# 3_ZynTra-Zynq-Config.net
KiCad netlist of a schematic drawn in Altium Designer
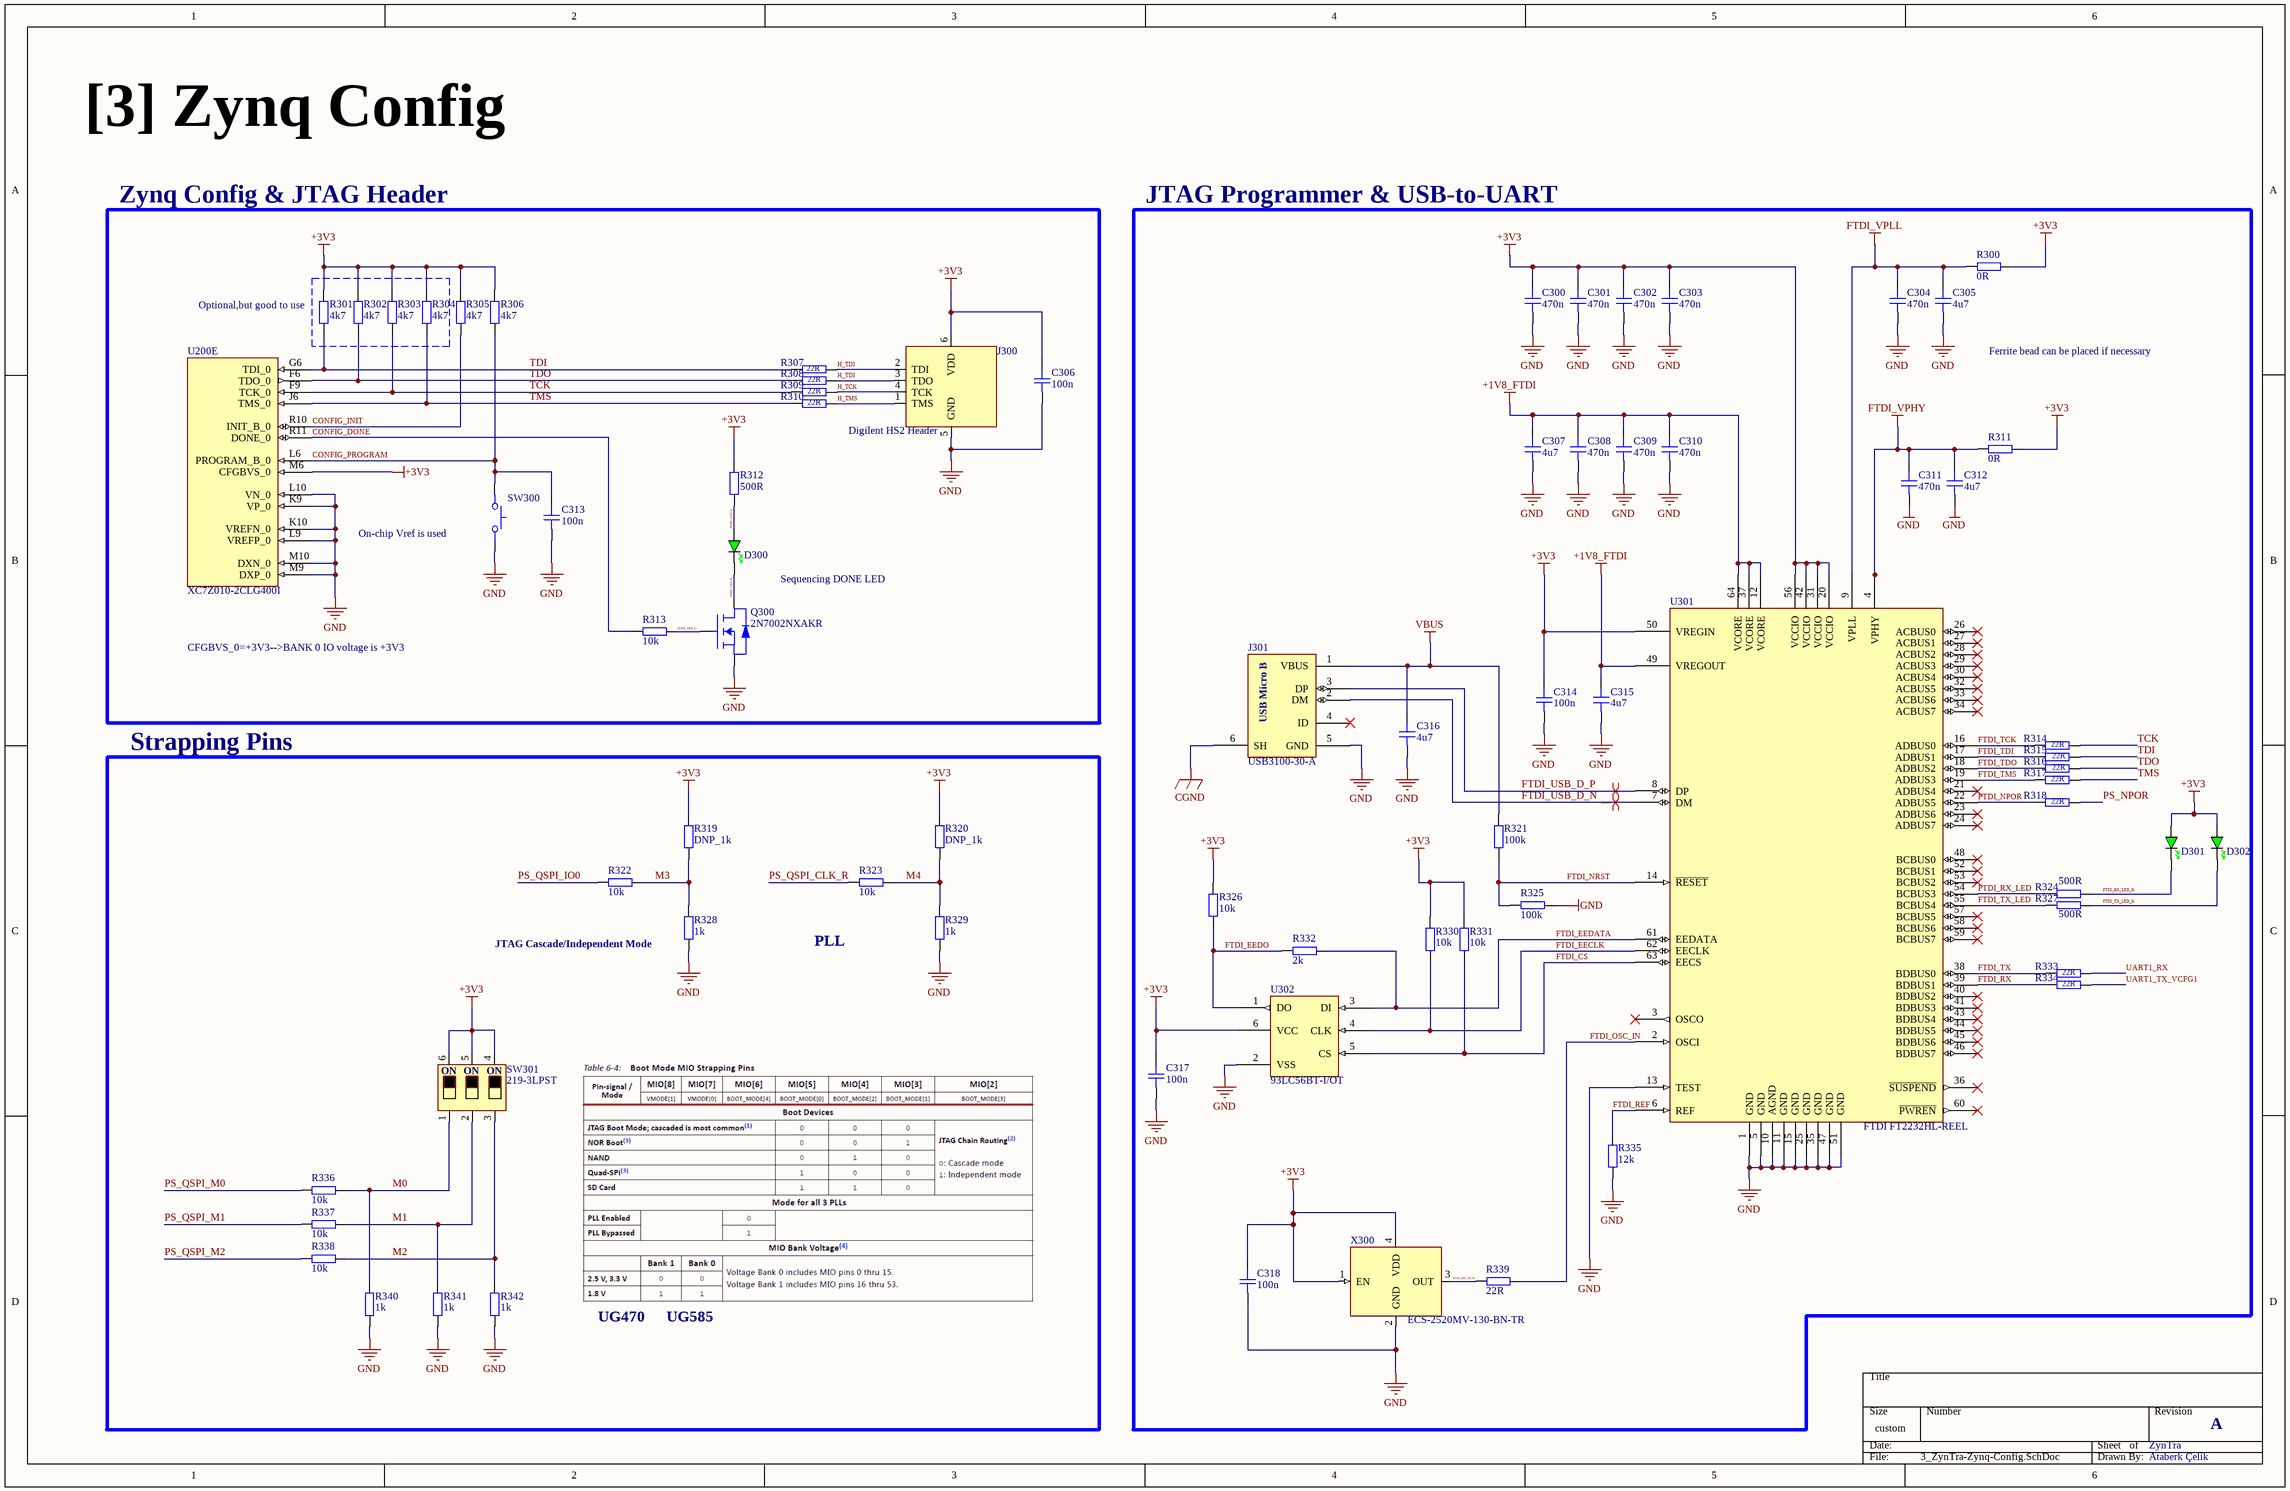
[diagram p0: 3_ZynTra-Zynq-Config.SchDoc]

(export (version "E")
  (design (tool "Eeschema 10.0.6"))
  (components
    (comp (ref "C300")
      (value "470n")
      (footprint "CAP_0201")
      (description "Capacitor SMD 0201")
      (libsource (lib "Schematic-Lib-PhilsLab") (part "CAP_0201"))
    )
    (comp (ref "C301")
      (value "470n")
      (footprint "CAP_0201")
      (description "Capacitor SMD 0201")
      (libsource (lib "Schematic-Lib-PhilsLab") (part "CAP_0201"))
    )
    (comp (ref "C302")
      (value "470n")
      (footprint "CAP_0201")
      (description "Capacitor SMD 0201")
      (libsource (lib "Schematic-Lib-PhilsLab") (part "CAP_0201"))
    )
    (comp (ref "C303")
      (value "470n")
      (footprint "CAP_0201")
      (description "Capacitor SMD 0201")
      (libsource (lib "Schematic-Lib-PhilsLab") (part "CAP_0201"))
    )
    (comp (ref "C304")
      (value "470n")
      (footprint "CAP_0201")
      (description "Capacitor SMD 0201")
      (libsource (lib "Schematic-Lib-PhilsLab") (part "CAP_0201"))
    )
    (comp (ref "C305")
      (value "4u7")
      (footprint "CAP_0402")
      (description "Capacitor SMD 0402")
      (libsource (lib "Schematic-Lib-PhilsLab") (part "CAP_0402"))
    )
    (comp (ref "C306")
      (value "100n")
      (footprint "CAP_0201")
      (description "Capacitor SMD 0201")
      (libsource (lib "Schematic-Lib-PhilsLab") (part "CAP_0201"))
    )
    (comp (ref "C307")
      (value "4u7")
      (footprint "CAP_0402")
      (description "Capacitor SMD 0402")
      (libsource (lib "Schematic-Lib-PhilsLab") (part "CAP_0402"))
    )
    (comp (ref "C308")
      (value "470n")
      (footprint "CAP_0201")
      (description "Capacitor SMD 0201")
      (libsource (lib "Schematic-Lib-PhilsLab") (part "CAP_0201"))
    )
    (comp (ref "C309")
      (value "470n")
      (footprint "CAP_0201")
      (description "Capacitor SMD 0201")
      (libsource (lib "Schematic-Lib-PhilsLab") (part "CAP_0201"))
    )
    (comp (ref "C310")
      (value "470n")
      (footprint "CAP_0201")
      (description "Capacitor SMD 0201")
      (libsource (lib "Schematic-Lib-PhilsLab") (part "CAP_0201"))
    )
    (comp (ref "C311")
      (value "470n")
      (footprint "CAP_0201")
      (description "Capacitor SMD 0201")
      (libsource (lib "Schematic-Lib-PhilsLab") (part "CAP_0201"))
    )
    (comp (ref "C312")
      (value "4u7")
      (footprint "CAP_0402")
      (description "Capacitor SMD 0402")
      (libsource (lib "Schematic-Lib-PhilsLab") (part "CAP_0402"))
    )
    (comp (ref "C313")
      (value "100n")
      (footprint "CAP_0201")
      (description "Capacitor SMD 0201")
      (libsource (lib "Schematic-Lib-PhilsLab") (part "CAP_0201"))
    )
    (comp (ref "C314")
      (value "100n")
      (footprint "CAP_0201")
      (description "Capacitor SMD 0201")
      (libsource (lib "Schematic-Lib-PhilsLab") (part "CAP_0201"))
    )
    (comp (ref "C315")
      (value "4u7")
      (footprint "CAP_0402")
      (description "Capacitor SMD 0402")
      (libsource (lib "Schematic-Lib-PhilsLab") (part "CAP_0402"))
    )
    (comp (ref "C316")
      (value "4u7")
      (footprint "CAP_0402")
      (description "Capacitor SMD 0402")
      (libsource (lib "Schematic-Lib-PhilsLab") (part "CAP_0402"))
    )
    (comp (ref "C317")
      (value "100n")
      (footprint "CAP_0201")
      (description "Capacitor SMD 0201")
      (libsource (lib "Schematic-Lib-PhilsLab") (part "CAP_0201"))
    )
    (comp (ref "C318")
      (value "100n")
      (footprint "CAP_0201")
      (description "Capacitor SMD 0201")
      (libsource (lib "Schematic-Lib-PhilsLab") (part "CAP_0201"))
    )
    (comp (ref "D300")
      (value "GREEN")
      (footprint "LED_0603_GREEN")
      (description "LED 0603 GREEN SMD")
      (libsource (lib "Schematic-Lib-PhilsLab") (part "LED_0603_GREEN"))
    )
    (comp (ref "D301")
      (value "GREEN")
      (footprint "LED_0603_GREEN")
      (description "LED 0603 GREEN SMD")
      (libsource (lib "Schematic-Lib-PhilsLab") (part "LED_0603_GREEN"))
    )
    (comp (ref "D302")
      (value "GREEN")
      (footprint "LED_0603_GREEN")
      (description "LED 0603 GREEN SMD")
      (libsource (lib "Schematic-Lib-PhilsLab") (part "LED_0603_GREEN"))
    )
    (comp (ref "J300")
      (value "Digilent HS2 Header")
      (footprint "DIGILENT_HS2")
      (description "Digilent HS2 6-Pin 2.54mm Pitch Header")
      (fields
        (field (name "MANUFACTURER") "Amphenol FCI")
        (field (name "MANUFACTURER PART NUMBER") "68000-406HLF")
      )
      (libsource (lib "Schematic-Lib-PhilsLab") (part "Digilent_HS2_Header"))
    )
    (comp (ref "J301")
      (value "USB3100-30-A")
      (footprint "USB3100-30-A")
      (description "Micro USB Receptacle, Type B, Surface Mount, Horizontal")
      (libsource (lib "AtaSchLib") (part "USB3100-30-A"))
    )
    (comp (ref "Q300")
      (value "2N7002NXAKR")
      (footprint "SSM3J338R,LF-SOT23-F")
      (description "MOSFET N-Channel Vds=60V Id=300mA with ESD Protection")
      (fields (field (name "MANUFACTURER") "Nexperia"))
      (libsource (lib "Schematic-Lib-PhilsLab") (part "2N7002NXAKR"))
    )
    (comp (ref "R300")
      (value "0R")
      (footprint "RES_0402")
      (description "Resistor SMD 0402")
      (libsource (lib "Schematic-Lib-PhilsLab") (part "RES_0402"))
    )
    (comp (ref "R301")
      (value "4k7")
      (footprint "RES_0201")
      (description "Resistor SMD 0201")
      (libsource (lib "Schematic-Lib-PhilsLab") (part "RES_0201"))
    )
    (comp (ref "R302")
      (value "4k7")
      (footprint "RES_0201")
      (description "Resistor SMD 0201")
      (libsource (lib "Schematic-Lib-PhilsLab") (part "RES_0201"))
    )
    (comp (ref "R303")
      (value "4k7")
      (footprint "RES_0201")
      (description "Resistor SMD 0201")
      (libsource (lib "Schematic-Lib-PhilsLab") (part "RES_0201"))
    )
    (comp (ref "R304")
      (value "4k7")
      (footprint "RES_0201")
      (description "Resistor SMD 0201")
      (libsource (lib "Schematic-Lib-PhilsLab") (part "RES_0201"))
    )
    (comp (ref "R305")
      (value "4k7")
      (footprint "RES_0201")
      (description "Resistor SMD 0201")
      (libsource (lib "Schematic-Lib-PhilsLab") (part "RES_0201"))
    )
    (comp (ref "R306")
      (value "4k7")
      (footprint "RES_0201")
      (description "Resistor SMD 0201")
      (libsource (lib "Schematic-Lib-PhilsLab") (part "RES_0201"))
    )
    (comp (ref "R307")
      (value "22R")
      (footprint "RES_0402")
      (description "Resistor SMD 0402")
      (libsource (lib "Schematic-Lib-PhilsLab") (part "RES_0402"))
    )
    (comp (ref "R308")
      (value "22R")
      (footprint "RES_0402")
      (description "Resistor SMD 0402")
      (libsource (lib "Schematic-Lib-PhilsLab") (part "RES_0402"))
    )
    (comp (ref "R309")
      (value "22R")
      (footprint "RES_0402")
      (description "Resistor SMD 0402")
      (libsource (lib "Schematic-Lib-PhilsLab") (part "RES_0402"))
    )
    (comp (ref "R310")
      (value "22R")
      (footprint "RES_0402")
      (description "Resistor SMD 0402")
      (libsource (lib "Schematic-Lib-PhilsLab") (part "RES_0402"))
    )
    (comp (ref "R311")
      (value "0R")
      (footprint "RES_0402")
      (description "Resistor SMD 0402")
      (libsource (lib "Schematic-Lib-PhilsLab") (part "RES_0402"))
    )
    (comp (ref "R312")
      (value "500R")
      (footprint "RES_0402")
      (description "Resistor SMD 0402")
      (libsource (lib "Schematic-Lib-PhilsLab") (part "RES_0402"))
    )
    (comp (ref "R313")
      (value "10k")
      (footprint "RES_0402")
      (description "Resistor SMD 0402")
      (libsource (lib "Schematic-Lib-PhilsLab") (part "RES_0402"))
    )
    (comp (ref "R314")
      (value "22R")
      (footprint "RES_0402")
      (description "Resistor SMD 0402")
      (libsource (lib "Schematic-Lib-PhilsLab") (part "RES_0402"))
    )
    (comp (ref "R315")
      (value "22R")
      (footprint "RES_0402")
      (description "Resistor SMD 0402")
      (libsource (lib "Schematic-Lib-PhilsLab") (part "RES_0402"))
    )
    (comp (ref "R316")
      (value "22R")
      (footprint "RES_0402")
      (description "Resistor SMD 0402")
      (libsource (lib "Schematic-Lib-PhilsLab") (part "RES_0402"))
    )
    (comp (ref "R317")
      (value "22R")
      (footprint "RES_0402")
      (description "Resistor SMD 0402")
      (libsource (lib "Schematic-Lib-PhilsLab") (part "RES_0402"))
    )
    (comp (ref "R318")
      (value "22R")
      (footprint "RES_0402")
      (description "Resistor SMD 0402")
      (libsource (lib "Schematic-Lib-PhilsLab") (part "RES_0402"))
    )
    (comp (ref "R319")
      (value "DNP_1k")
      (footprint "RES_0402")
      (description "Resistor SMD 0402")
      (libsource (lib "Schematic-Lib-PhilsLab") (part "RES_0402"))
    )
    (comp (ref "R320")
      (value "DNP_1k")
      (footprint "RES_0402")
      (description "Resistor SMD 0402")
      (libsource (lib "Schematic-Lib-PhilsLab") (part "RES_0402"))
    )
    (comp (ref "R321")
      (value "100k")
      (footprint "RES_0402")
      (description "Resistor SMD 0402")
      (libsource (lib "Schematic-Lib-PhilsLab") (part "RES_0402"))
    )
    (comp (ref "R322")
      (value "10k")
      (footprint "RES_0402")
      (description "Resistor SMD 0402")
      (libsource (lib "Schematic-Lib-PhilsLab") (part "RES_0402"))
    )
    (comp (ref "R323")
      (value "10k")
      (footprint "RES_0402")
      (description "Resistor SMD 0402")
      (libsource (lib "Schematic-Lib-PhilsLab") (part "RES_0402"))
    )
    (comp (ref "R324")
      (value "500R")
      (footprint "RES_0402")
      (description "Resistor SMD 0402")
      (libsource (lib "Schematic-Lib-PhilsLab") (part "RES_0402"))
    )
    (comp (ref "R325")
      (value "100k")
      (footprint "RES_0402")
      (description "Resistor SMD 0402")
      (libsource (lib "Schematic-Lib-PhilsLab") (part "RES_0402"))
    )
    (comp (ref "R326")
      (value "10k")
      (footprint "RES_0402")
      (description "Resistor SMD 0402")
      (libsource (lib "Schematic-Lib-PhilsLab") (part "RES_0402"))
    )
    (comp (ref "R327")
      (value "500R")
      (footprint "RES_0402")
      (description "Resistor SMD 0402")
      (libsource (lib "Schematic-Lib-PhilsLab") (part "RES_0402"))
    )
    (comp (ref "R328")
      (value "1k")
      (footprint "RES_0402")
      (description "Resistor SMD 0402")
      (libsource (lib "Schematic-Lib-PhilsLab") (part "RES_0402"))
    )
    (comp (ref "R329")
      (value "1k")
      (footprint "RES_0402")
      (description "Resistor SMD 0402")
      (libsource (lib "Schematic-Lib-PhilsLab") (part "RES_0402"))
    )
    (comp (ref "R330")
      (value "10k")
      (footprint "RES_0402")
      (description "Resistor SMD 0402")
      (libsource (lib "Schematic-Lib-PhilsLab") (part "RES_0402"))
    )
    (comp (ref "R331")
      (value "10k")
      (footprint "RES_0402")
      (description "Resistor SMD 0402")
      (libsource (lib "Schematic-Lib-PhilsLab") (part "RES_0402"))
    )
    (comp (ref "R332")
      (value "2k")
      (footprint "RES_0402")
      (description "Resistor SMD 0402")
      (libsource (lib "Schematic-Lib-PhilsLab") (part "RES_0402"))
    )
    (comp (ref "R333")
      (value "22R")
      (footprint "RES_0402")
      (description "Resistor SMD 0402")
      (libsource (lib "Schematic-Lib-PhilsLab") (part "RES_0402"))
    )
    (comp (ref "R334")
      (value "22R")
      (footprint "RES_0402")
      (description "Resistor SMD 0402")
      (libsource (lib "Schematic-Lib-PhilsLab") (part "RES_0402"))
    )
    (comp (ref "R335")
      (value "12k")
      (footprint "RES_0402")
      (description "Resistor SMD 0402")
      (libsource (lib "Schematic-Lib-PhilsLab") (part "RES_0402"))
    )
    (comp (ref "R336")
      (value "10k")
      (footprint "RES_0402")
      (description "Resistor SMD 0402")
      (libsource (lib "Schematic-Lib-PhilsLab") (part "RES_0402"))
    )
    (comp (ref "R337")
      (value "10k")
      (footprint "RES_0402")
      (description "Resistor SMD 0402")
      (libsource (lib "Schematic-Lib-PhilsLab") (part "RES_0402"))
    )
    (comp (ref "R338")
      (value "10k")
      (footprint "RES_0402")
      (description "Resistor SMD 0402")
      (libsource (lib "Schematic-Lib-PhilsLab") (part "RES_0402"))
    )
    (comp (ref "R339")
      (value "22R")
      (footprint "RES_0402")
      (description "Resistor SMD 0402")
      (libsource (lib "Schematic-Lib-PhilsLab") (part "RES_0402"))
    )
    (comp (ref "R340")
      (value "1k")
      (footprint "RES_0402")
      (description "Resistor SMD 0402")
      (libsource (lib "Schematic-Lib-PhilsLab") (part "RES_0402"))
    )
    (comp (ref "R341")
      (value "1k")
      (footprint "RES_0402")
      (description "Resistor SMD 0402")
      (libsource (lib "Schematic-Lib-PhilsLab") (part "RES_0402"))
    )
    (comp (ref "R342")
      (value "1k")
      (footprint "RES_0402")
      (description "Resistor SMD 0402")
      (libsource (lib "Schematic-Lib-PhilsLab") (part "RES_0402"))
    )
    (comp (ref "SW300")
      (value "SKRPANE010")
      (footprint "SKRPANE010")
      (description "Tactile Switch SMD SPST")
      (fields (field (name "MANUFACTURER") "Alps Alpine"))
      (libsource (lib "Schematic-Lib-PhilsLab") (part "SKRPANE010"))
    )
    (comp (ref "SW301")
      (value "219-3LPST")
      (footprint "219-3LPST")
      (description "DIP Switches SPST 3x")
      (fields (field (name "MANUFACTURER") "CTS"))
      (libsource (lib "Schematic-Lib-PhilsLab") (part "219-3LPST"))
    )
    (comp (ref "U200")
      (value "XC7Z010-2CLG400I")
      (footprint "CLG400, 0.8mm, 17x17")
      (fields (field (name "MANUFACTURER") "AMD / Xilinx"))
      (libsource (lib "AtaSchLib") (part "XC7Z010-2CLG400I"))
    )
    (comp (ref "U301")
      (value "FTDI FT2232HL-REEL")
      (footprint "LQFP, 64, 12x12mm")
      (fields (field (name "MANUFACTURER") "FTDI") (field (name "MANUFACTURER PART NUMBER") "FT2232HL-REEL"))
      (libsource (lib "AtaSchLib") (part "FTDI FT2232HL-REEL"))
    )
    (comp (ref "U302")
      (value "93LC56BT-I/OT")
      (footprint "SOT23-6, 1.60x2.90")
      (description "2-Kbit Microwire Compatible Serial EEPROM")
      (fields (field (name "MANUFACTURER") "Microchip"))
      (libsource (lib "AtaSchLib") (part "93LC56BT-I/OT"))
    )
    (comp (ref "X300")
      (value "ECS-2520MV-130-BN-TR")
      (footprint "XTAL_2520")
      (fields (field (name "MANUFACTURER") "ECS"))
      (libsource (lib "Schematic-Lib-PhilsLab") (part "ECS-2520MV-130-BN-TR"))
    )
  )
  (nets
    (net (code "1") (name "+1V8_FTDI") (class "Default")
      (node (ref "C307") (pin "2") (pinfunction "2_2") (pintype "passive"))
      (node (ref "C308") (pin "2") (pinfunction "2_2") (pintype "passive"))
      (node (ref "C309") (pin "2") (pinfunction "2_2") (pintype "passive"))
      (node (ref "C310") (pin "2") (pinfunction "2_2") (pintype "passive"))
      (node (ref "C315") (pin "2") (pinfunction "2_2") (pintype "passive"))
      (node (ref "U301") (pin "12") (pinfunction "VCORE_12") (pintype "power_in"))
      (node (ref "U301") (pin "37") (pinfunction "VCORE_37") (pintype "power_in"))
      (node (ref "U301") (pin "49") (pinfunction "VREGOUT_49") (pintype "power_in"))
      (node (ref "U301") (pin "64") (pinfunction "VCORE_64") (pintype "power_in"))
    )
    (net (code "2") (name "+3V3") (class "Default")
      (node (ref "C300") (pin "2") (pinfunction "2_2") (pintype "passive"))
      (node (ref "C301") (pin "2") (pinfunction "2_2") (pintype "passive"))
      (node (ref "C302") (pin "2") (pinfunction "2_2") (pintype "passive"))
      (node (ref "C303") (pin "2") (pinfunction "2_2") (pintype "passive"))
      (node (ref "C306") (pin "2") (pinfunction "2_2") (pintype "passive"))
      (node (ref "C314") (pin "2") (pinfunction "2_2") (pintype "passive"))
      (node (ref "C317") (pin "2") (pinfunction "2_2") (pintype "passive"))
      (node (ref "C318") (pin "2") (pinfunction "2_2") (pintype "passive"))
      (node (ref "D301") (pin "A") (pinfunction "A_A") (pintype "passive"))
      (node (ref "D302") (pin "A") (pinfunction "A_A") (pintype "passive"))
      (node (ref "J300") (pin "6") (pinfunction "VDD_6") (pintype "power_in"))
      (node (ref "R300") (pin "2") (pinfunction "2_2") (pintype "passive"))
      (node (ref "R301") (pin "2") (pinfunction "2_2") (pintype "passive"))
      (node (ref "R302") (pin "2") (pinfunction "2_2") (pintype "passive"))
      (node (ref "R303") (pin "2") (pinfunction "2_2") (pintype "passive"))
      (node (ref "R304") (pin "2") (pinfunction "2_2") (pintype "passive"))
      (node (ref "R305") (pin "2") (pinfunction "2_2") (pintype "passive"))
      (node (ref "R306") (pin "2") (pinfunction "2_2") (pintype "passive"))
      (node (ref "R311") (pin "2") (pinfunction "2_2") (pintype "passive"))
      (node (ref "R312") (pin "1") (pinfunction "1_1") (pintype "passive"))
      (node (ref "R319") (pin "2") (pinfunction "2_2") (pintype "passive"))
      (node (ref "R320") (pin "2") (pinfunction "2_2") (pintype "passive"))
      (node (ref "R326") (pin "2") (pinfunction "2_2") (pintype "passive"))
      (node (ref "R330") (pin "2") (pinfunction "2_2") (pintype "passive"))
      (node (ref "R331") (pin "2") (pinfunction "2_2") (pintype "passive"))
      (node (ref "SW301") (pin "4") (pinfunction "4_4") (pintype "passive"))
      (node (ref "SW301") (pin "5") (pinfunction "5_5") (pintype "passive"))
      (node (ref "SW301") (pin "6") (pinfunction "6_6") (pintype "passive"))
      (node (ref "U200") (pin "M6") (pinfunction "CFGBVS_0_M6") (pintype "input"))
      (node (ref "U301") (pin "20") (pinfunction "VCCIO_20") (pintype "power_in"))
      (node (ref "U301") (pin "31") (pinfunction "VCCIO_31") (pintype "power_in"))
      (node (ref "U301") (pin "42") (pinfunction "VCCIO_42") (pintype "power_in"))
      (node (ref "U301") (pin "50") (pinfunction "VREGIN_50") (pintype "power_in"))
      (node (ref "U301") (pin "56") (pinfunction "VCCIO_56") (pintype "power_in"))
      (node (ref "U302") (pin "6") (pinfunction "VCC_6") (pintype "power_in"))
      (node (ref "X300") (pin "1") (pinfunction "EN_1") (pintype "input"))
      (node (ref "X300") (pin "4") (pinfunction "VDD_4") (pintype "power_in"))
    )
    (net (code "3") (name "/CONFIG_DONE") (class "Default")
      (node (ref "R313") (pin "1") (pinfunction "1_1") (pintype "passive"))
      (node (ref "U200") (pin "R11") (pinfunction "DONE_0_R11") (pintype "bidirectional"))
    )
    (net (code "4") (name "/CONFIG_INIT") (class "Default")
      (node (ref "R305") (pin "1") (pinfunction "1_1") (pintype "passive"))
      (node (ref "U200") (pin "R10") (pinfunction "INIT_B_0_R10") (pintype "bidirectional"))
    )
    (net (code "5") (name "/CONFIG_PROGRAM") (class "Default")
      (node (ref "C313") (pin "2") (pinfunction "2_2") (pintype "passive"))
      (node (ref "R306") (pin "1") (pinfunction "1_1") (pintype "passive"))
      (node (ref "SW300") (pin "12") (pintype "passive"))
      (node (ref "U200") (pin "L6") (pinfunction "PROGRAM_B_0_L6") (pintype "input"))
    )
    (net (code "6") (name "/DONE_LED_A") (class "Default")
      (node (ref "D300") (pin "A") (pinfunction "A_A") (pintype "passive"))
      (node (ref "R312") (pin "2") (pinfunction "2_2") (pintype "passive"))
    )
    (net (code "7") (name "/DONE_LED_K") (class "Default")
      (node (ref "D300") (pin "K") (pinfunction "K_K") (pintype "passive"))
      (node (ref "Q300") (pin "D") (pinfunction "D_D") (pintype "passive"))
    )
    (net (code "8") (name "/DONE_MOS_G") (class "Default")
      (node (ref "Q300") (pin "G") (pinfunction "G_G") (pintype "passive"))
      (node (ref "R313") (pin "2") (pinfunction "2_2") (pintype "passive"))
    )
    (net (code "9") (name "/FTDI_CS") (class "Default")
      (node (ref "R331") (pin "1") (pinfunction "1_1") (pintype "passive"))
      (node (ref "U301") (pin "63") (pinfunction "EECS_63") (pintype "bidirectional"))
      (node (ref "U302") (pin "5") (pinfunction "CS_5") (pintype "input"))
    )
    (net (code "10") (name "/FTDI_EECLK") (class "Default")
      (node (ref "R330") (pin "1") (pinfunction "1_1") (pintype "passive"))
      (node (ref "U301") (pin "62") (pinfunction "EECLK_62") (pintype "bidirectional"))
      (node (ref "U302") (pin "4") (pinfunction "CLK_4") (pintype "input"))
    )
    (net (code "11") (name "/FTDI_EEDATA") (class "Default")
      (node (ref "R332") (pin "1") (pinfunction "1_1") (pintype "passive"))
      (node (ref "U301") (pin "61") (pinfunction "EEDATA_61") (pintype "bidirectional"))
      (node (ref "U302") (pin "3") (pinfunction "DI_3") (pintype "input"))
    )
    (net (code "12") (name "/FTDI_EEDO") (class "Default")
      (node (ref "R326") (pin "1") (pinfunction "1_1") (pintype "passive"))
      (node (ref "R332") (pin "2") (pinfunction "2_2") (pintype "passive"))
      (node (ref "U302") (pin "1") (pinfunction "DO_1") (pintype "output"))
    )
    (net (code "13") (name "/FTDI_NPOR") (class "Default")
      (node (ref "R318") (pin "2") (pinfunction "2_2") (pintype "passive"))
      (node (ref "U301") (pin "22") (pinfunction "ADBUS5_22") (pintype "bidirectional"))
    )
    (net (code "14") (name "/FTDI_NRST") (class "Default")
      (node (ref "R321") (pin "1") (pinfunction "1_1") (pintype "passive"))
      (node (ref "R325") (pin "2") (pinfunction "2_2") (pintype "passive"))
      (node (ref "U301") (pin "14") (pinfunction "~{RESET}_14") (pintype "input"))
    )
    (net (code "15") (name "/FTDI_OSC_IN") (class "Default")
      (node (ref "R339") (pin "1") (pinfunction "1_1") (pintype "passive"))
      (node (ref "U301") (pin "2") (pinfunction "OSCI_2") (pintype "input"))
    )
    (net (code "16") (name "/FTDI_OSC_IN_R") (class "Default")
      (node (ref "R339") (pin "2") (pinfunction "2_2") (pintype "passive"))
      (node (ref "X300") (pin "3") (pinfunction "OUT_3") (pintype "passive"))
    )
    (net (code "17") (name "/FTDI_REF") (class "Default")
      (node (ref "R335") (pin "2") (pinfunction "2_2") (pintype "passive"))
      (node (ref "U301") (pin "6") (pinfunction "REF_6") (pintype "input"))
    )
    (net (code "18") (name "/FTDI_RX") (class "Default")
      (node (ref "R334") (pin "2") (pinfunction "2_2") (pintype "passive"))
      (node (ref "U301") (pin "39") (pinfunction "BDBUS1_39") (pintype "bidirectional"))
    )
    (net (code "19") (name "/FTDI_RX_LED") (class "Default")
      (node (ref "R324") (pin "2") (pinfunction "2_2") (pintype "passive"))
      (node (ref "U301") (pin "54") (pinfunction "BCBUS3_54") (pintype "bidirectional"))
    )
    (net (code "20") (name "/FTDI_RX_LED_K") (class "Default")
      (node (ref "D301") (pin "K") (pinfunction "K_K") (pintype "passive"))
      (node (ref "R324") (pin "1") (pinfunction "1_1") (pintype "passive"))
    )
    (net (code "21") (name "/FTDI_TCK") (class "Default")
      (node (ref "R314") (pin "2") (pinfunction "2_2") (pintype "passive"))
      (node (ref "U301") (pin "16") (pinfunction "ADBUS0_16") (pintype "bidirectional"))
    )
    (net (code "22") (name "/FTDI_TDI") (class "Default")
      (node (ref "R315") (pin "2") (pinfunction "2_2") (pintype "passive"))
      (node (ref "U301") (pin "17") (pinfunction "ADBUS1_17") (pintype "bidirectional"))
    )
    (net (code "23") (name "/FTDI_TDO") (class "Default")
      (node (ref "R316") (pin "2") (pinfunction "2_2") (pintype "passive"))
      (node (ref "U301") (pin "18") (pinfunction "ADBUS2_18") (pintype "bidirectional"))
    )
    (net (code "24") (name "/FTDI_TMS") (class "Default")
      (node (ref "R317") (pin "2") (pinfunction "2_2") (pintype "passive"))
      (node (ref "U301") (pin "19") (pinfunction "ADBUS3_19") (pintype "bidirectional"))
    )
    (net (code "25") (name "/FTDI_TX") (class "Default")
      (node (ref "R333") (pin "2") (pinfunction "2_2") (pintype "passive"))
      (node (ref "U301") (pin "38") (pinfunction "BDBUS0_38") (pintype "bidirectional"))
    )
    (net (code "26") (name "/FTDI_TX_LED") (class "Default")
      (node (ref "R327") (pin "2") (pinfunction "2_2") (pintype "passive"))
      (node (ref "U301") (pin "55") (pinfunction "BCBUS4_55") (pintype "bidirectional"))
    )
    (net (code "27") (name "/FTDI_TX_LED_K") (class "Default")
      (node (ref "D302") (pin "K") (pinfunction "K_K") (pintype "passive"))
      (node (ref "R327") (pin "1") (pinfunction "1_1") (pintype "passive"))
    )
    (net (code "28") (name "/FTDI_USB_D_N") (class "Default")
      (node (ref "J301") (pin "2") (pinfunction "DM_2") (pintype "bidirectional"))
      (node (ref "U301") (pin "7") (pinfunction "DM_7") (pintype "bidirectional"))
    )
    (net (code "29") (name "/FTDI_USB_D_P") (class "Default")
      (node (ref "J301") (pin "3") (pinfunction "DP_3") (pintype "bidirectional"))
      (node (ref "U301") (pin "8") (pinfunction "DP_8") (pintype "bidirectional"))
    )
    (net (code "30") (name "/H_TCK") (class "Default")
      (node (ref "J300") (pin "4") (pinfunction "TCK_4") (pintype "passive"))
      (node (ref "R309") (pin "2") (pinfunction "2_2") (pintype "passive"))
    )
    (net (code "31") (name "/H_TDI") (class "Default")
      (node (ref "J300") (pin "2") (pinfunction "TDI_2") (pintype "passive"))
      (node (ref "J300") (pin "3") (pinfunction "TDO_3") (pintype "passive"))
      (node (ref "R307") (pin "2") (pinfunction "2_2") (pintype "passive"))
      (node (ref "R308") (pin "2") (pinfunction "2_2") (pintype "passive"))
    )
    (net (code "32") (name "/H_TMS") (class "Default")
      (node (ref "J300") (pin "1") (pinfunction "TMS_1") (pintype "passive"))
      (node (ref "R310") (pin "2") (pinfunction "2_2") (pintype "passive"))
    )
    (net (code "33") (name "/M0") (class "Default")
      (node (ref "R336") (pin "2") (pinfunction "2_2") (pintype "passive"))
      (node (ref "R340") (pin "2") (pinfunction "2_2") (pintype "passive"))
      (node (ref "SW301") (pin "1") (pinfunction "1_1") (pintype "passive"))
    )
    (net (code "34") (name "/M1") (class "Default")
      (node (ref "R337") (pin "2") (pinfunction "2_2") (pintype "passive"))
      (node (ref "R341") (pin "2") (pinfunction "2_2") (pintype "passive"))
      (node (ref "SW301") (pin "2") (pinfunction "2_2") (pintype "passive"))
    )
    (net (code "35") (name "/M2") (class "Default")
      (node (ref "R338") (pin "2") (pinfunction "2_2") (pintype "passive"))
      (node (ref "R342") (pin "2") (pinfunction "2_2") (pintype "passive"))
      (node (ref "SW301") (pin "3") (pinfunction "3_3") (pintype "passive"))
    )
    (net (code "36") (name "/M3") (class "Default")
      (node (ref "R319") (pin "1") (pinfunction "1_1") (pintype "passive"))
      (node (ref "R322") (pin "2") (pinfunction "2_2") (pintype "passive"))
      (node (ref "R328") (pin "2") (pinfunction "2_2") (pintype "passive"))
    )
    (net (code "37") (name "/M4") (class "Default")
      (node (ref "R320") (pin "1") (pinfunction "1_1") (pintype "passive"))
      (node (ref "R323") (pin "2") (pinfunction "2_2") (pintype "passive"))
      (node (ref "R329") (pin "2") (pinfunction "2_2") (pintype "passive"))
    )
    (net (code "38") (name "/PS_NPOR") (class "Default")
      (node (ref "R318") (pin "1") (pinfunction "1_1") (pintype "passive"))
    )
    (net (code "39") (name "/PS_QSPI_CLK_R") (class "Default")
      (node (ref "R323") (pin "1") (pinfunction "1_1") (pintype "passive"))
    )
    (net (code "40") (name "/PS_QSPI_IO0") (class "Default")
      (node (ref "R322") (pin "1") (pinfunction "1_1") (pintype "passive"))
    )
    (net (code "41") (name "/PS_QSPI_M0") (class "Default")
      (node (ref "R336") (pin "1") (pinfunction "1_1") (pintype "passive"))
    )
    (net (code "42") (name "/PS_QSPI_M1") (class "Default")
      (node (ref "R337") (pin "1") (pinfunction "1_1") (pintype "passive"))
    )
    (net (code "43") (name "/PS_QSPI_M2") (class "Default")
      (node (ref "R338") (pin "1") (pinfunction "1_1") (pintype "passive"))
    )
    (net (code "44") (name "/TCK") (class "Default")
      (node (ref "R303") (pin "1") (pinfunction "1_1") (pintype "passive"))
      (node (ref "R309") (pin "1") (pinfunction "1_1") (pintype "passive"))
      (node (ref "R314") (pin "1") (pinfunction "1_1") (pintype "passive"))
      (node (ref "U200") (pin "F9") (pinfunction "TCK_0_F9") (pintype "input"))
    )
    (net (code "45") (name "/TDI") (class "Default")
      (node (ref "R301") (pin "1") (pinfunction "1_1") (pintype "passive"))
      (node (ref "R307") (pin "1") (pinfunction "1_1") (pintype "passive"))
      (node (ref "R315") (pin "1") (pinfunction "1_1") (pintype "passive"))
      (node (ref "U200") (pin "G6") (pinfunction "TDI_0_G6") (pintype "input"))
    )
    (net (code "46") (name "/TDO") (class "Default")
      (node (ref "R302") (pin "1") (pinfunction "1_1") (pintype "passive"))
      (node (ref "R308") (pin "1") (pinfunction "1_1") (pintype "passive"))
      (node (ref "R316") (pin "1") (pinfunction "1_1") (pintype "passive"))
      (node (ref "U200") (pin "F6") (pinfunction "TDO_0_F6") (pintype "output"))
    )
    (net (code "47") (name "/TMS") (class "Default")
      (node (ref "R304") (pin "1") (pinfunction "1_1") (pintype "passive"))
      (node (ref "R310") (pin "1") (pinfunction "1_1") (pintype "passive"))
      (node (ref "R317") (pin "1") (pinfunction "1_1") (pintype "passive"))
      (node (ref "U200") (pin "J6") (pinfunction "TMS_0_J6") (pintype "input"))
    )
    (net (code "48") (name "/UART1_RX") (class "Default")
      (node (ref "R333") (pin "1") (pinfunction "1_1") (pintype "passive"))
    )
    (net (code "49") (name "/UART1_TX_VCFG1") (class "Default")
      (node (ref "R334") (pin "1") (pinfunction "1_1") (pintype "passive"))
    )
    (net (code "50") (name "CGND") (class "Default")
      (node (ref "J301") (pin "6") (pinfunction "SH_6") (pintype "power_in"))
    )
    (net (code "51") (name "FTDI_VPHY") (class "Default")
      (node (ref "C311") (pin "2") (pinfunction "2_2") (pintype "passive"))
      (node (ref "C312") (pin "2") (pinfunction "2_2") (pintype "passive"))
      (node (ref "R311") (pin "1") (pinfunction "1_1") (pintype "passive"))
      (node (ref "U301") (pin "4") (pinfunction "VPHY_4") (pintype "power_in"))
    )
    (net (code "52") (name "FTDI_VPLL") (class "Default")
      (node (ref "C304") (pin "2") (pinfunction "2_2") (pintype "passive"))
      (node (ref "C305") (pin "2") (pinfunction "2_2") (pintype "passive"))
      (node (ref "R300") (pin "1") (pinfunction "1_1") (pintype "passive"))
      (node (ref "U301") (pin "9") (pinfunction "VPLL_9") (pintype "power_in"))
    )
    (net (code "53") (name "GND") (class "Default")
      (node (ref "C300") (pin "1") (pinfunction "1_1") (pintype "passive"))
      (node (ref "C301") (pin "1") (pinfunction "1_1") (pintype "passive"))
      (node (ref "C302") (pin "1") (pinfunction "1_1") (pintype "passive"))
      (node (ref "C303") (pin "1") (pinfunction "1_1") (pintype "passive"))
      (node (ref "C304") (pin "1") (pinfunction "1_1") (pintype "passive"))
      (node (ref "C305") (pin "1") (pinfunction "1_1") (pintype "passive"))
      (node (ref "C306") (pin "1") (pinfunction "1_1") (pintype "passive"))
      (node (ref "C307") (pin "1") (pinfunction "1_1") (pintype "passive"))
      (node (ref "C308") (pin "1") (pinfunction "1_1") (pintype "passive"))
      (node (ref "C309") (pin "1") (pinfunction "1_1") (pintype "passive"))
      (node (ref "C310") (pin "1") (pinfunction "1_1") (pintype "passive"))
      (node (ref "C311") (pin "1") (pinfunction "1_1") (pintype "passive"))
      (node (ref "C312") (pin "1") (pinfunction "1_1") (pintype "passive"))
      (node (ref "C313") (pin "1") (pinfunction "1_1") (pintype "passive"))
      (node (ref "C314") (pin "1") (pinfunction "1_1") (pintype "passive"))
      (node (ref "C315") (pin "1") (pinfunction "1_1") (pintype "passive"))
      (node (ref "C316") (pin "1") (pinfunction "1_1") (pintype "passive"))
      (node (ref "C317") (pin "1") (pinfunction "1_1") (pintype "passive"))
      (node (ref "C318") (pin "1") (pinfunction "1_1") (pintype "passive"))
      (node (ref "J300") (pin "5") (pinfunction "GND_5") (pintype "power_in"))
      (node (ref "J301") (pin "5") (pinfunction "GND_5") (pintype "power_in"))
      (node (ref "Q300") (pin "S") (pinfunction "S_S") (pintype "passive"))
      (node (ref "R325") (pin "1") (pinfunction "1_1") (pintype "passive"))
      (node (ref "R328") (pin "1") (pinfunction "1_1") (pintype "passive"))
      (node (ref "R329") (pin "1") (pinfunction "1_1") (pintype "passive"))
      (node (ref "R335") (pin "1") (pinfunction "1_1") (pintype "passive"))
      (node (ref "R340") (pin "1") (pinfunction "1_1") (pintype "passive"))
      (node (ref "R341") (pin "1") (pinfunction "1_1") (pintype "passive"))
      (node (ref "R342") (pin "1") (pinfunction "1_1") (pintype "passive"))
      (node (ref "SW300") (pin "34") (pintype "passive"))
      (node (ref "U200") (pin "K10") (pinfunction "VREFN_0_K10") (pintype "input"))
      (node (ref "U200") (pin "K9") (pinfunction "VP_0_K9") (pintype "input"))
      (node (ref "U200") (pin "L10") (pinfunction "VN_0_L10") (pintype "input"))
      (node (ref "U200") (pin "L9") (pinfunction "VREFP_0_L9") (pintype "input"))
      (node (ref "U200") (pin "M10") (pinfunction "DXN_0_M10") (pintype "input"))
      (node (ref "U200") (pin "M9") (pinfunction "DXP_0_M9") (pintype "input"))
      (node (ref "U301") (pin "1") (pinfunction "GND_1") (pintype "power_in"))
      (node (ref "U301") (pin "10") (pinfunction "AGND_10") (pintype "power_in"))
      (node (ref "U301") (pin "11") (pinfunction "GND_11") (pintype "power_in"))
      (node (ref "U301") (pin "13") (pinfunction "TEST_13") (pintype "input"))
      (node (ref "U301") (pin "15") (pinfunction "GND_15") (pintype "power_in"))
      (node (ref "U301") (pin "25") (pinfunction "GND_25") (pintype "power_in"))
      (node (ref "U301") (pin "35") (pinfunction "GND_35") (pintype "power_in"))
      (node (ref "U301") (pin "47") (pinfunction "GND_47") (pintype "power_in"))
      (node (ref "U301") (pin "5") (pinfunction "GND_5") (pintype "power_in"))
      (node (ref "U301") (pin "51") (pinfunction "GND_51") (pintype "power_in"))
      (node (ref "U302") (pin "2") (pinfunction "VSS_2") (pintype "power_in"))
      (node (ref "X300") (pin "2") (pinfunction "GND_2") (pintype "power_in"))
    )
    (net (code "54") (name "VBUS") (class "Default")
      (node (ref "C316") (pin "2") (pinfunction "2_2") (pintype "passive"))
      (node (ref "J301") (pin "1") (pinfunction "VBUS_1") (pintype "power_in"))
      (node (ref "R321") (pin "2") (pinfunction "2_2") (pintype "passive"))
    )
    (net (code "55") (name "unconnected-(J301-ID-Pad4)") (class "Default")
      (node (ref "J301") (pin "4") (pinfunction "ID_4") (pintype "passive+no_connect"))
    )
    (net (code "56") (name "unconnected-(U301-ACBUS0-Pad26)") (class "Default")
      (node (ref "U301") (pin "26") (pinfunction "ACBUS0_26") (pintype "bidirectional+no_connect"))
    )
    (net (code "57") (name "unconnected-(U301-ACBUS1-Pad27)") (class "Default")
      (node (ref "U301") (pin "27") (pinfunction "ACBUS1_27") (pintype "bidirectional+no_connect"))
    )
    (net (code "58") (name "unconnected-(U301-ACBUS2-Pad28)") (class "Default")
      (node (ref "U301") (pin "28") (pinfunction "ACBUS2_28") (pintype "bidirectional+no_connect"))
    )
    (net (code "59") (name "unconnected-(U301-ACBUS3-Pad29)") (class "Default")
      (node (ref "U301") (pin "29") (pinfunction "ACBUS3_29") (pintype "bidirectional+no_connect"))
    )
    (net (code "60") (name "unconnected-(U301-ACBUS4-Pad30)") (class "Default")
      (node (ref "U301") (pin "30") (pinfunction "ACBUS4_30") (pintype "bidirectional+no_connect"))
    )
    (net (code "61") (name "unconnected-(U301-ACBUS5-Pad32)") (class "Default")
      (node (ref "U301") (pin "32") (pinfunction "ACBUS5_32") (pintype "bidirectional+no_connect"))
    )
    (net (code "62") (name "unconnected-(U301-ACBUS6-Pad33)") (class "Default")
      (node (ref "U301") (pin "33") (pinfunction "ACBUS6_33") (pintype "bidirectional+no_connect"))
    )
    (net (code "63") (name "unconnected-(U301-ACBUS7-Pad34)") (class "Default")
      (node (ref "U301") (pin "34") (pinfunction "ACBUS7_34") (pintype "bidirectional+no_connect"))
    )
    (net (code "64") (name "unconnected-(U301-ADBUS4-Pad21)") (class "Default")
      (node (ref "U301") (pin "21") (pinfunction "ADBUS4_21") (pintype "bidirectional+no_connect"))
    )
    (net (code "65") (name "unconnected-(U301-ADBUS6-Pad23)") (class "Default")
      (node (ref "U301") (pin "23") (pinfunction "ADBUS6_23") (pintype "bidirectional+no_connect"))
    )
    (net (code "66") (name "unconnected-(U301-ADBUS7-Pad24)") (class "Default")
      (node (ref "U301") (pin "24") (pinfunction "ADBUS7_24") (pintype "bidirectional+no_connect"))
    )
    (net (code "67") (name "unconnected-(U301-BCBUS0-Pad48)") (class "Default")
      (node (ref "U301") (pin "48") (pinfunction "BCBUS0_48") (pintype "bidirectional+no_connect"))
    )
    (net (code "68") (name "unconnected-(U301-BCBUS1-Pad52)") (class "Default")
      (node (ref "U301") (pin "52") (pinfunction "BCBUS1_52") (pintype "bidirectional+no_connect"))
    )
    (net (code "69") (name "unconnected-(U301-BCBUS2-Pad53)") (class "Default")
      (node (ref "U301") (pin "53") (pinfunction "BCBUS2_53") (pintype "bidirectional+no_connect"))
    )
    (net (code "70") (name "unconnected-(U301-BCBUS5-Pad57)") (class "Default")
      (node (ref "U301") (pin "57") (pinfunction "BCBUS5_57") (pintype "bidirectional+no_connect"))
    )
    (net (code "71") (name "unconnected-(U301-BCBUS6-Pad58)") (class "Default")
      (node (ref "U301") (pin "58") (pinfunction "BCBUS6_58") (pintype "bidirectional+no_connect"))
    )
    (net (code "72") (name "unconnected-(U301-BCBUS7-Pad59)") (class "Default")
      (node (ref "U301") (pin "59") (pinfunction "BCBUS7_59") (pintype "bidirectional+no_connect"))
    )
    (net (code "73") (name "unconnected-(U301-BDBUS2-Pad40)") (class "Default")
      (node (ref "U301") (pin "40") (pinfunction "BDBUS2_40") (pintype "bidirectional+no_connect"))
    )
    (net (code "74") (name "unconnected-(U301-BDBUS3-Pad41)") (class "Default")
      (node (ref "U301") (pin "41") (pinfunction "BDBUS3_41") (pintype "bidirectional+no_connect"))
    )
    (net (code "75") (name "unconnected-(U301-BDBUS4-Pad43)") (class "Default")
      (node (ref "U301") (pin "43") (pinfunction "BDBUS4_43") (pintype "bidirectional+no_connect"))
    )
    (net (code "76") (name "unconnected-(U301-BDBUS5-Pad44)") (class "Default")
      (node (ref "U301") (pin "44") (pinfunction "BDBUS5_44") (pintype "bidirectional+no_connect"))
    )
    (net (code "77") (name "unconnected-(U301-BDBUS6-Pad45)") (class "Default")
      (node (ref "U301") (pin "45") (pinfunction "BDBUS6_45") (pintype "bidirectional+no_connect"))
    )
    (net (code "78") (name "unconnected-(U301-BDBUS7-Pad46)") (class "Default")
      (node (ref "U301") (pin "46") (pinfunction "BDBUS7_46") (pintype "bidirectional+no_connect"))
    )
    (net (code "79") (name "unconnected-(U301-OSCO-Pad3)") (class "Default")
      (node (ref "U301") (pin "3") (pinfunction "OSCO_3") (pintype "output+no_connect"))
    )
    (net (code "80") (name "unconnected-(U301-~{PWREN}-Pad60)") (class "Default")
      (node (ref "U301") (pin "60") (pinfunction "~{PWREN}_60") (pintype "output+no_connect"))
    )
    (net (code "81") (name "unconnected-(U301-~{SUSPEND}-Pad36)") (class "Default")
      (node (ref "U301") (pin "36") (pinfunction "~{SUSPEND}_36") (pintype "output+no_connect"))
    )
  )
)
